# panda.net
KiCad netlist of a schematic drawn in Altium Designer
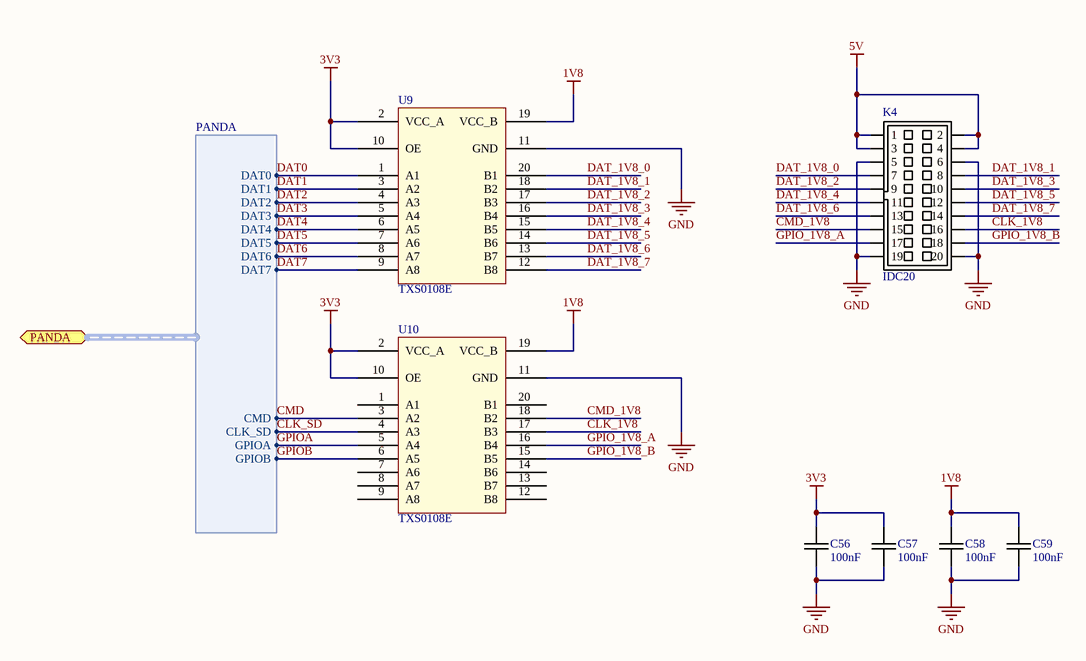
[diagram p0: panda.SchDoc]

(export (version "E")
  (design (tool "Eeschema 10.0.6"))
  (components
    (comp (ref "C56")
      (value "100nF")
      (footprint "0603C-GENERIC")
      (description "GENERIC CAPACITOR NON POLARISED 0603")
      (fields (field (name "TOLERANCE") "±10%") (field (name "MANUFACTURER PART NUMBER") "C1608X7R1H103K"))
      (libsource (lib "vh_Altium Library") (part "0603C-100NF-50V-X7R-TDK"))
    )
    (comp (ref "C57")
      (value "100nF")
      (footprint "0603C-GENERIC")
      (description "GENERIC CAPACITOR NON POLARISED 0603")
      (fields (field (name "TOLERANCE") "±10%") (field (name "MANUFACTURER PART NUMBER") "C1608X7R1H103K"))
      (libsource (lib "vh_Altium Library") (part "0603C-100NF-50V-X7R-TDK"))
    )
    (comp (ref "C58")
      (value "100nF")
      (footprint "0603C-GENERIC")
      (description "GENERIC CAPACITOR NON POLARISED 0603")
      (fields (field (name "TOLERANCE") "±10%") (field (name "MANUFACTURER PART NUMBER") "C1608X7R1H103K"))
      (libsource (lib "vh_Altium Library") (part "0603C-100NF-50V-X7R-TDK"))
    )
    (comp (ref "C59")
      (value "100nF")
      (footprint "0603C-GENERIC")
      (description "GENERIC CAPACITOR NON POLARISED 0603")
      (fields (field (name "TOLERANCE") "±10%") (field (name "MANUFACTURER PART NUMBER") "C1608X7R1H103K"))
      (libsource (lib "vh_Altium Library") (part "0603C-100NF-50V-X7R-TDK"))
    )
    (comp (ref "K4")
      (value "IDC20")
      (footprint "IDC20-B")
      (description "CONN HEADER LOW-PRO 20POS GOLD")
      (fields (field (name "MANUFACTURER") "Assmann Electronics Inc"))
      (libsource (lib "vh_Altium Library") (part "IDC20"))
    )
    (comp (ref "U9")
      (value "TXS0108E")
      (footprint "TSOP65P640-20BM")
      (libsource (lib "camera_board") (part "TXS0108E"))
    )
    (comp (ref "U10")
      (value "TXS0108E")
      (footprint "TSOP65P640-20BM")
      (libsource (lib "camera_board") (part "TXS0108E"))
    )
  )
  (nets
    (net (code "2") (name "/CLK_1V8") (class "Default")
      (node (ref "K4") (pin "16") (pinfunction "16_16") (pintype "passive"))
      (node (ref "U10") (pin "17") (pinfunction "B3_17") (pintype "passive"))
    )
    (net (code "3") (name "/CLK_SD") (class "Default")
      (node (ref "U10") (pin "4") (pinfunction "A3_4") (pintype "passive"))
    )
    (net (code "4") (name "/CMD") (class "Default")
      (node (ref "U10") (pin "3") (pinfunction "A2_3") (pintype "passive"))
    )
    (net (code "5") (name "/CMD_1V8") (class "Default")
      (node (ref "K4") (pin "15") (pinfunction "15_15") (pintype "passive"))
      (node (ref "U10") (pin "18") (pinfunction "B2_18") (pintype "passive"))
    )
    (net (code "6") (name "/DAT0") (class "Default")
      (node (ref "U9") (pin "1") (pinfunction "A1_1") (pintype "passive"))
    )
    (net (code "7") (name "/DAT1") (class "Default")
      (node (ref "U9") (pin "3") (pinfunction "A2_3") (pintype "passive"))
    )
    (net (code "8") (name "/DAT2") (class "Default")
      (node (ref "U9") (pin "4") (pinfunction "A3_4") (pintype "passive"))
    )
    (net (code "9") (name "/DAT3") (class "Default")
      (node (ref "U9") (pin "5") (pinfunction "A4_5") (pintype "passive"))
    )
    (net (code "10") (name "/DAT4") (class "Default")
      (node (ref "U9") (pin "6") (pinfunction "A5_6") (pintype "passive"))
    )
    (net (code "11") (name "/DAT5") (class "Default")
      (node (ref "U9") (pin "7") (pinfunction "A6_7") (pintype "passive"))
    )
    (net (code "12") (name "/DAT6") (class "Default")
      (node (ref "U9") (pin "8") (pinfunction "A7_8") (pintype "passive"))
    )
    (net (code "13") (name "/DAT7") (class "Default")
      (node (ref "U9") (pin "9") (pinfunction "A8_9") (pintype "passive"))
    )
    (net (code "14") (name "/DAT_1V8_0") (class "Default")
      (node (ref "K4") (pin "7") (pinfunction "7_7") (pintype "passive"))
      (node (ref "U9") (pin "20") (pinfunction "B1_20") (pintype "passive"))
    )
    (net (code "15") (name "/DAT_1V8_1") (class "Default")
      (node (ref "K4") (pin "8") (pinfunction "8_8") (pintype "passive"))
      (node (ref "U9") (pin "18") (pinfunction "B2_18") (pintype "passive"))
    )
    (net (code "16") (name "/DAT_1V8_2") (class "Default")
      (node (ref "K4") (pin "9") (pinfunction "9_9") (pintype "passive"))
      (node (ref "U9") (pin "17") (pinfunction "B3_17") (pintype "passive"))
    )
    (net (code "17") (name "/DAT_1V8_3") (class "Default")
      (node (ref "K4") (pin "10") (pinfunction "10_10") (pintype "passive"))
      (node (ref "U9") (pin "16") (pinfunction "B4_16") (pintype "passive"))
    )
    (net (code "18") (name "/DAT_1V8_4") (class "Default")
      (node (ref "K4") (pin "11") (pinfunction "11_11") (pintype "passive"))
      (node (ref "U9") (pin "15") (pinfunction "B5_15") (pintype "passive"))
    )
    (net (code "19") (name "/DAT_1V8_5") (class "Default")
      (node (ref "K4") (pin "12") (pinfunction "12_12") (pintype "passive"))
      (node (ref "U9") (pin "14") (pinfunction "B6_14") (pintype "passive"))
    )
    (net (code "20") (name "/DAT_1V8_6") (class "Default")
      (node (ref "K4") (pin "13") (pinfunction "13_13") (pintype "passive"))
      (node (ref "U9") (pin "13") (pinfunction "B7_13") (pintype "passive"))
    )
    (net (code "21") (name "/DAT_1V8_7") (class "Default")
      (node (ref "K4") (pin "14") (pinfunction "14_14") (pintype "passive"))
      (node (ref "U9") (pin "12") (pinfunction "B8_12") (pintype "passive"))
    )
    (net (code "22") (name "/GPIOA") (class "Default")
      (node (ref "U10") (pin "5") (pinfunction "A4_5") (pintype "passive"))
    )
    (net (code "23") (name "/GPIOB") (class "Default")
      (node (ref "U10") (pin "6") (pinfunction "A5_6") (pintype "passive"))
    )
    (net (code "24") (name "/GPIO_1V8_A") (class "Default")
      (node (ref "K4") (pin "17") (pinfunction "17_17") (pintype "passive"))
      (node (ref "U10") (pin "16") (pinfunction "B4_16") (pintype "passive"))
    )
    (net (code "25") (name "/GPIO_1V8_B") (class "Default")
      (node (ref "K4") (pin "18") (pinfunction "18_18") (pintype "passive"))
      (node (ref "U10") (pin "15") (pinfunction "B5_15") (pintype "passive"))
    )
    (net (code "27") (name "1V8") (class "Default")
      (node (ref "C58") (pin "1") (pintype "passive"))
      (node (ref "C59") (pin "1") (pintype "passive"))
      (node (ref "U10") (pin "19") (pinfunction "VCC_B_19") (pintype "passive"))
      (node (ref "U9") (pin "19") (pinfunction "VCC_B_19") (pintype "passive"))
    )
    (net (code "28") (name "3V3") (class "Default")
      (node (ref "C56") (pin "1") (pintype "passive"))
      (node (ref "C57") (pin "1") (pintype "passive"))
      (node (ref "U10") (pin "10") (pinfunction "OE_10") (pintype "passive"))
      (node (ref "U10") (pin "2") (pinfunction "VCC_A_2") (pintype "passive"))
      (node (ref "U9") (pin "10") (pinfunction "OE_10") (pintype "passive"))
      (node (ref "U9") (pin "2") (pinfunction "VCC_A_2") (pintype "passive"))
    )
    (net (code "29") (name "5V") (class "Default")
      (node (ref "K4") (pin "1") (pinfunction "1_1") (pintype "passive"))
      (node (ref "K4") (pin "2") (pinfunction "2_2") (pintype "passive"))
      (node (ref "K4") (pin "3") (pinfunction "3_3") (pintype "passive"))
      (node (ref "K4") (pin "4") (pinfunction "4_4") (pintype "passive"))
    )
    (net (code "30") (name "GND") (class "Default")
      (node (ref "C56") (pin "2") (pintype "passive"))
      (node (ref "C57") (pin "2") (pintype "passive"))
      (node (ref "C58") (pin "2") (pintype "passive"))
      (node (ref "C59") (pin "2") (pintype "passive"))
      (node (ref "K4") (pin "19") (pinfunction "19_19") (pintype "passive"))
      (node (ref "K4") (pin "20") (pinfunction "20_20") (pintype "passive"))
      (node (ref "K4") (pin "5") (pinfunction "5_5") (pintype "passive"))
      (node (ref "K4") (pin "6") (pinfunction "6_6") (pintype "passive"))
      (node (ref "U10") (pin "11") (pinfunction "GND_11") (pintype "passive"))
      (node (ref "U9") (pin "11") (pinfunction "GND_11") (pintype "passive"))
    )
    (net (code "31") (name "unconnected-(U10-A1-Pad1)") (class "Default")
      (node (ref "U10") (pin "1") (pinfunction "A1_1") (pintype "passive"))
    )
    (net (code "32") (name "unconnected-(U10-A6-Pad7)") (class "Default")
      (node (ref "U10") (pin "7") (pinfunction "A6_7") (pintype "passive"))
    )
    (net (code "33") (name "unconnected-(U10-A7-Pad8)") (class "Default")
      (node (ref "U10") (pin "8") (pinfunction "A7_8") (pintype "passive"))
    )
    (net (code "34") (name "unconnected-(U10-A8-Pad9)") (class "Default")
      (node (ref "U10") (pin "9") (pinfunction "A8_9") (pintype "passive"))
    )
    (net (code "35") (name "unconnected-(U10-B1-Pad20)") (class "Default")
      (node (ref "U10") (pin "20") (pinfunction "B1_20") (pintype "passive"))
    )
    (net (code "36") (name "unconnected-(U10-B6-Pad14)") (class "Default")
      (node (ref "U10") (pin "14") (pinfunction "B6_14") (pintype "passive"))
    )
    (net (code "37") (name "unconnected-(U10-B7-Pad13)") (class "Default")
      (node (ref "U10") (pin "13") (pinfunction "B7_13") (pintype "passive"))
    )
    (net (code "38") (name "unconnected-(U10-B8-Pad12)") (class "Default")
      (node (ref "U10") (pin "12") (pinfunction "B8_12") (pintype "passive"))
    )
  )
)
